# phy.net
KiCad netlist of a schematic drawn in Altium Designer
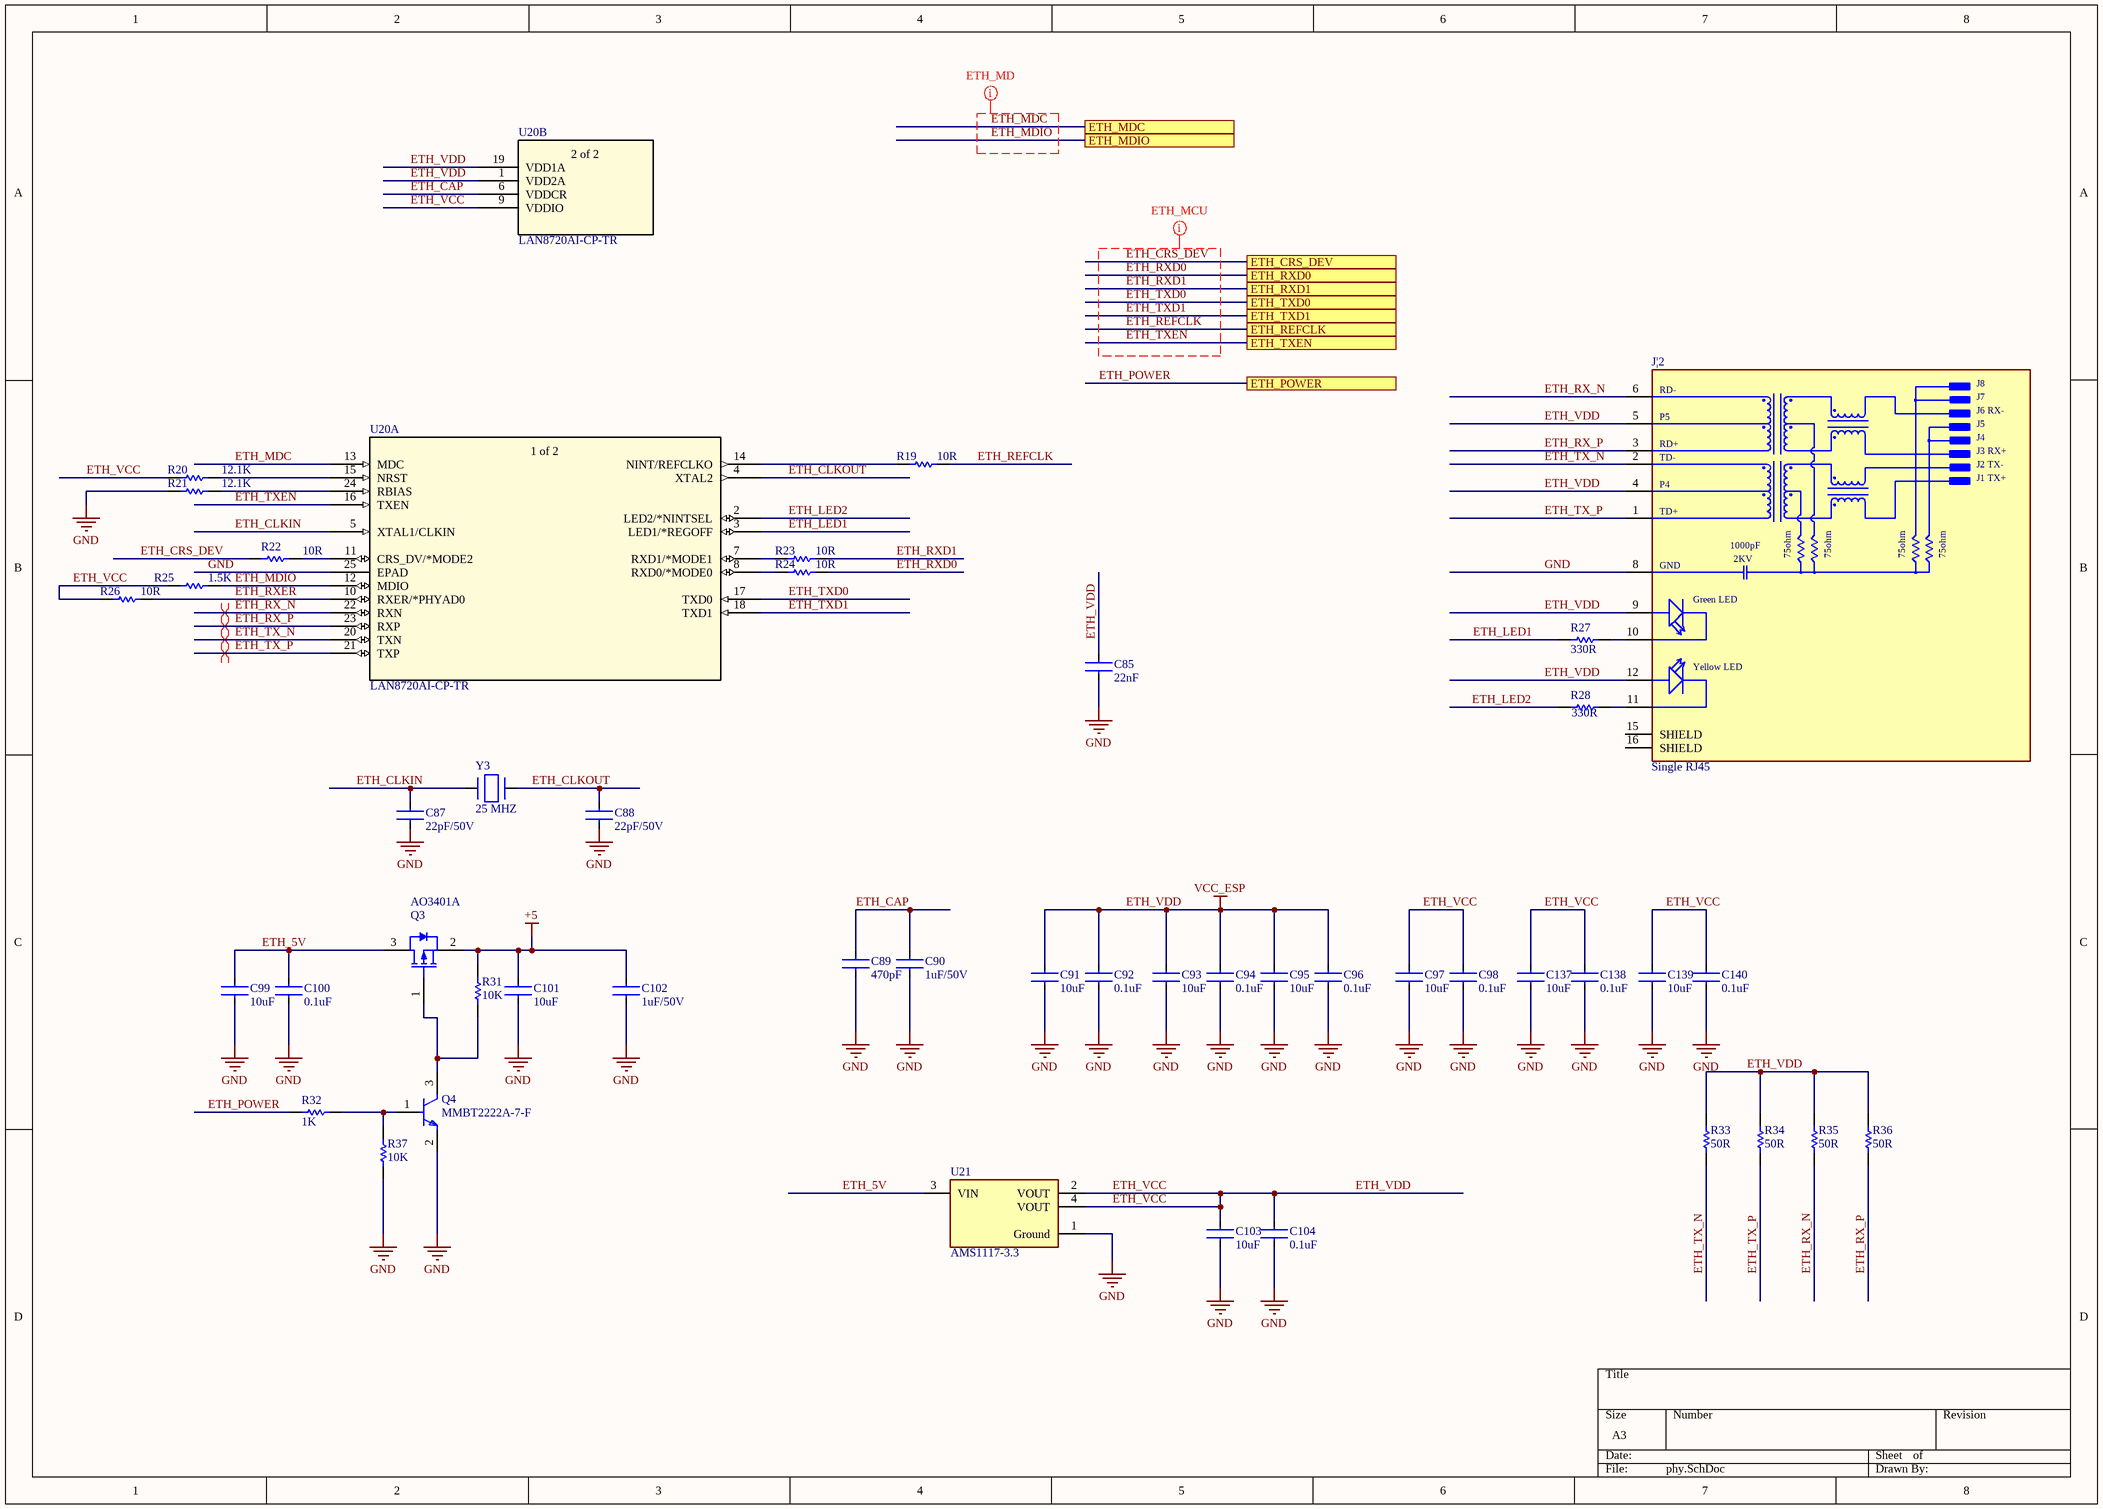
[diagram p0: phy.SchDoc]

(export (version "E")
  (design (tool "Eeschema 10.0.6"))
  (components
    (comp (ref "C85")
      (value "22nF")
      (footprint "C0402")
      (description "Cap Ceramic 22nF 50V C0G 5% SMD 1206 125°C Paper T/R")
      (fields
        (field (name "MANUFACTURER") "Samsung")
        (field (name "MANUFACTURER PART NUMBER") "CL31B223KBCNNNC")
      )
      (libsource (lib "afra") (part "CL31B223KBCNNNC"))
    )
    (comp (ref "C87")
      (value "22pF/50V")
      (footprint "C0402")
      (description "Cap Ceramic 22pF 50V C0G 5% SMD 1206 125°C Paper T/R")
      (fields
        (field (name "MANUFACTURER") "Samsung")
        (field (name "MANUFACTURER PART NUMBER") "CL31C220JBCNNNC")
      )
      (libsource (lib "afra") (part "CL31C220JBCNNNC"))
    )
    (comp (ref "C88")
      (value "22pF/50V")
      (footprint "C0402")
      (description "Cap Ceramic 22pF 50V C0G 5% SMD 1206 125°C Paper T/R")
      (fields
        (field (name "MANUFACTURER") "Samsung")
        (field (name "MANUFACTURER PART NUMBER") "CL31C220JBCNNNC")
      )
      (libsource (lib "afra") (part "CL31C220JBCNNNC"))
    )
    (comp (ref "C89")
      (value "470pF")
      (footprint "C0402")
      (description "Cap Ceramic 470pF 50V C0G 5% SMD 1206 125°C Paper T/R")
      (fields
        (field (name "MANUFACTURER") "Samsung")
        (field (name "MANUFACTURER PART NUMBER") "CL31C220JBCNNNC")
      )
      (libsource (lib "afra") (part "CL31B471KBCNNNC"))
    )
    (comp (ref "C90")
      (value "1uF/50V")
      (footprint "C0402")
      (description "CAP CER 1UF 50V X7R 1206")
      (fields
        (field (name "MANUFACTURER") "Samsung")
        (field (name "MANUFACTURER PART NUMBER") "CL31B105KBHNNNE")
      )
      (libsource (lib "afra") (part "CL31B105KBHNNNE"))
    )
    (comp (ref "C91")
      (value "10uF")
      (footprint "C0402")
      (description "Cap Ceramic 10uF 16V X7R 10% Pad SMD 1206 125°C T/R")
      (fields
        (field (name "MANUFACTURER") "Samsung")
        (field (name "MANUFACTURER PART NUMBER") "CL31B106KOHNNNE")
      )
      (libsource (lib "afra") (part "CL31B106KOHNNNE"))
    )
    (comp (ref "C92")
      (value "0.1uF")
      (footprint "C0402")
      (description "Ceramic capacitor SMD-1206 100nF /50V X7R# K +-10%, Samsung, RoHS")
      (fields
        (field (name "MANUFACTURER") "Samsung")
        (field (name "MANUFACTURER PART NUMBER") "CL31B104KBCNNNC")
      )
      (libsource (lib "afra") (part "CL31B104KBCNNNC"))
    )
    (comp (ref "C93")
      (value "10uF")
      (footprint "C0402")
      (description "Cap Ceramic 10uF 16V X7R 10% Pad SMD 1206 125°C T/R")
      (fields
        (field (name "MANUFACTURER") "Samsung")
        (field (name "MANUFACTURER PART NUMBER") "CL31B106KOHNNNE")
      )
      (libsource (lib "afra") (part "CL31B106KOHNNNE"))
    )
    (comp (ref "C94")
      (value "0.1uF")
      (footprint "C0402")
      (description "Ceramic capacitor SMD-1206 100nF /50V X7R# K +-10%, Samsung, RoHS")
      (fields
        (field (name "MANUFACTURER") "Samsung")
        (field (name "MANUFACTURER PART NUMBER") "CL31B104KBCNNNC")
      )
      (libsource (lib "afra") (part "CL31B104KBCNNNC"))
    )
    (comp (ref "C95")
      (value "10uF")
      (footprint "C0402")
      (description "Cap Ceramic 10uF 16V X7R 10% Pad SMD 1206 125°C T/R")
      (fields
        (field (name "MANUFACTURER") "Samsung")
        (field (name "MANUFACTURER PART NUMBER") "CL31B106KOHNNNE")
      )
      (libsource (lib "afra") (part "CL31B106KOHNNNE"))
    )
    (comp (ref "C96")
      (value "0.1uF")
      (footprint "C0402")
      (description "Ceramic capacitor SMD-1206 100nF /50V X7R# K +-10%, Samsung, RoHS")
      (fields
        (field (name "MANUFACTURER") "Samsung")
        (field (name "MANUFACTURER PART NUMBER") "CL31B104KBCNNNC")
      )
      (libsource (lib "afra") (part "CL31B104KBCNNNC"))
    )
    (comp (ref "C97")
      (value "10uF")
      (footprint "C0402")
      (description "Cap Ceramic 10uF 16V X7R 10% Pad SMD 1206 125°C T/R")
      (fields
        (field (name "MANUFACTURER") "Samsung")
        (field (name "MANUFACTURER PART NUMBER") "CL31B106KOHNNNE")
      )
      (libsource (lib "afra") (part "CL31B106KOHNNNE"))
    )
    (comp (ref "C98")
      (value "0.1uF")
      (footprint "C0402")
      (description "Ceramic capacitor SMD-1206 100nF /50V X7R# K +-10%, Samsung, RoHS")
      (fields
        (field (name "MANUFACTURER") "Samsung")
        (field (name "MANUFACTURER PART NUMBER") "CL31B104KBCNNNC")
      )
      (libsource (lib "afra") (part "CL31B104KBCNNNC"))
    )
    (comp (ref "C99")
      (value "10uF")
      (footprint "C0402")
      (description "Cap Ceramic 10uF 16V X7R 10% Pad SMD 1206 125°C T/R")
      (fields
        (field (name "MANUFACTURER") "Samsung")
        (field (name "MANUFACTURER PART NUMBER") "CL31B106KOHNNNE")
      )
      (libsource (lib "afra") (part "CL31B106KOHNNNE"))
    )
    (comp (ref "C100")
      (value "0.1uF")
      (footprint "C0402")
      (description "Ceramic capacitor SMD-1206 100nF /50V X7R# K +-10%, Samsung, RoHS")
      (fields
        (field (name "MANUFACTURER") "Samsung")
        (field (name "MANUFACTURER PART NUMBER") "CL31B104KBCNNNC")
      )
      (libsource (lib "afra") (part "CL31B104KBCNNNC"))
    )
    (comp (ref "C101")
      (value "10uF")
      (footprint "C0402")
      (description "Cap Ceramic 10uF 16V X7R 10% Pad SMD 1206 125°C T/R")
      (fields
        (field (name "MANUFACTURER") "Samsung")
        (field (name "MANUFACTURER PART NUMBER") "CL31B106KOHNNNE")
      )
      (libsource (lib "afra") (part "CL31B106KOHNNNE"))
    )
    (comp (ref "C102")
      (value "1uF/50V")
      (footprint "C0402")
      (description "CAP CER 1UF 50V X7R 1206")
      (fields
        (field (name "MANUFACTURER") "Samsung")
        (field (name "MANUFACTURER PART NUMBER") "CL31B105KBHNNNE")
      )
      (libsource (lib "afra") (part "CL31B105KBHNNNE"))
    )
    (comp (ref "C103")
      (value "10uF")
      (footprint "C0402")
      (description "Cap Ceramic 10uF 16V X7R 10% Pad SMD 1206 125°C T/R")
      (fields
        (field (name "MANUFACTURER") "Samsung")
        (field (name "MANUFACTURER PART NUMBER") "CL31B106KOHNNNE")
      )
      (libsource (lib "afra") (part "CL31B106KOHNNNE"))
    )
    (comp (ref "C104")
      (value "0.1uF")
      (footprint "C0402")
      (description "Ceramic capacitor SMD-1206 100nF /50V X7R# K +-10%, Samsung, RoHS")
      (fields
        (field (name "MANUFACTURER") "Samsung")
        (field (name "MANUFACTURER PART NUMBER") "CL31B104KBCNNNC")
      )
      (libsource (lib "afra") (part "CL31B104KBCNNNC"))
    )
    (comp (ref "C137")
      (value "10uF")
      (footprint "C0402")
      (description "Cap Ceramic 10uF 16V X7R 10% Pad SMD 1206 125°C T/R")
      (fields
        (field (name "MANUFACTURER") "Samsung")
        (field (name "MANUFACTURER PART NUMBER") "CL31B106KOHNNNE")
      )
      (libsource (lib "afra") (part "CL31B106KOHNNNE"))
    )
    (comp (ref "C138")
      (value "0.1uF")
      (footprint "C0402")
      (description "Ceramic capacitor SMD-1206 100nF /50V X7R# K +-10%, Samsung, RoHS")
      (fields
        (field (name "MANUFACTURER") "Samsung")
        (field (name "MANUFACTURER PART NUMBER") "CL31B104KBCNNNC")
      )
      (libsource (lib "afra") (part "CL31B104KBCNNNC"))
    )
    (comp (ref "C139")
      (value "10uF")
      (footprint "C0402")
      (description "Cap Ceramic 10uF 16V X7R 10% Pad SMD 1206 125°C T/R")
      (fields
        (field (name "MANUFACTURER") "Samsung")
        (field (name "MANUFACTURER PART NUMBER") "CL31B106KOHNNNE")
      )
      (libsource (lib "afra") (part "CL31B106KOHNNNE"))
    )
    (comp (ref "C140")
      (value "0.1uF")
      (footprint "C0402")
      (description "Ceramic capacitor SMD-1206 100nF /50V X7R# K +-10%, Samsung, RoHS")
      (fields
        (field (name "MANUFACTURER") "Samsung")
        (field (name "MANUFACTURER PART NUMBER") "CL31B104KBCNNNC")
      )
      (libsource (lib "afra") (part "CL31B104KBCNNNC"))
    )
    (comp (ref "J¦2")
      (value "Single RJ45")
      (footprint "HANRUN_HR911105A")
      (description "HR911105A Ethernet Interface Arduino Platform Evaluation Expansion Board")
      (fields (field (name "MP") "HR911105A") (field (name "MF") "DFRobot"))
      (libsource (lib "afra") (part "HR911105A"))
    )
    (comp (ref "Q3")
      (value "AO3401A")
      (footprint "SOT-23-3L_AOS")
      (description "No Description Available")
      (fields (field (name "COPYRIGHT") "Copyright (C) 2022 Ultra Librarian. All rights reserved."))
      (libsource (lib "afra") (part "AO3401A"))
    )
    (comp (ref "Q4")
      (value "MMBT2222A-7-F")
      (footprint "SOT-23-3L_AOS")
      (description "NPN Ic=600mA Vceo=40V hfe=100~300 fT=300MHz P=310mW SOT-23")
      (fields (field (name "MANUFACTURER") "Diodes") (field (name "VOLTAGE") "40V"))
      (libsource (lib "afra") (part "MMBT2222A-7-F"))
    )
    (comp (ref "R19")
      (value "10R")
      (footprint "R0402")
      (description "Res Thick Film 1206 10 Ohm 1% 0.25W(1/4W) +/-200ppm/ßC Epoxy SMD T/R")
      (fields
        (field (name "MANUFACTURER") "Yageo")
        (field (name "MANUFACTURER PART NUMBER") "RC1206FR-0710RL")
      )
      (libsource (lib "afra") (part "RC1206FR-0710RL"))
    )
    (comp (ref "R20")
      (value "12.1K")
      (footprint "R0402")
      (description "Res Thick Film 1206 12.1K Ohm 1% 0.25W(1/4W) ±100ppm/C Pad SMD T/R")
      (fields
        (field (name "MANUFACTURER") "Yageo")
        (field (name "MANUFACTURER PART NUMBER") "RC1206FR-072K2L")
      )
      (libsource (lib "afra") (part "RC1206FR-0712K1L"))
    )
    (comp (ref "R21")
      (value "12.1K")
      (footprint "R0402")
      (description "Res Thick Film 1206 12.1K Ohm 1% 0.25W(1/4W) ±100ppm/C Pad SMD T/R")
      (fields
        (field (name "MANUFACTURER") "Yageo")
        (field (name "MANUFACTURER PART NUMBER") "RC1206FR-072K2L")
      )
      (libsource (lib "afra") (part "RC1206FR-0712K1L"))
    )
    (comp (ref "R22")
      (value "10R")
      (footprint "R0402")
      (description "Res Thick Film 1206 10 Ohm 1% 0.25W(1/4W) +/-200ppm/ßC Epoxy SMD T/R")
      (fields
        (field (name "MANUFACTURER") "Yageo")
        (field (name "MANUFACTURER PART NUMBER") "RC1206FR-0710RL")
      )
      (libsource (lib "afra") (part "RC1206FR-0710RL"))
    )
    (comp (ref "R23")
      (value "10R")
      (footprint "R0402")
      (description "Res Thick Film 1206 10 Ohm 1% 0.25W(1/4W) +/-200ppm/ßC Epoxy SMD T/R")
      (fields
        (field (name "MANUFACTURER") "Yageo")
        (field (name "MANUFACTURER PART NUMBER") "RC1206FR-0710RL")
      )
      (libsource (lib "afra") (part "RC1206FR-0710RL"))
    )
    (comp (ref "R24")
      (value "10R")
      (footprint "R0402")
      (description "Res Thick Film 1206 10 Ohm 1% 0.25W(1/4W) +/-200ppm/ßC Epoxy SMD T/R")
      (fields
        (field (name "MANUFACTURER") "Yageo")
        (field (name "MANUFACTURER PART NUMBER") "RC1206FR-0710RL")
      )
      (libsource (lib "afra") (part "RC1206FR-0710RL"))
    )
    (comp (ref "R25")
      (value "1.5K")
      (footprint "R0402")
      (description "In a Pack of 5000, 1.5K 1206 Thick Film SMD Resistor ±1% 0.25W - RC1206FR-071KL")
      (fields
        (field (name "MANUFACTURER") "Yageo")
        (field (name "MANUFACTURER PART NUMBER") "RC1206FR-071KL")
      )
      (libsource (lib "afra") (part "RC1206FR-071K5L"))
    )
    (comp (ref "R26")
      (value "10R")
      (footprint "R0402")
      (description "Res Thick Film 1206 10 Ohm 1% 0.25W(1/4W) +/-200ppm/ßC Epoxy SMD T/R")
      (fields
        (field (name "MANUFACTURER") "Yageo")
        (field (name "MANUFACTURER PART NUMBER") "RC1206FR-0710RL")
      )
      (libsource (lib "afra") (part "RC1206FR-0710RL"))
    )
    (comp (ref "R27")
      (value "330R")
      (footprint "R0402")
      (description "Res Thick Film 1206 330 Ohm 1% 0.25W(1/4W) ±100ppm/°C Pad SMD T/R")
      (fields
        (field (name "MANUFACTURER") "Yageo")
        (field (name "MANUFACTURER PART NUMBER") "RC1206FR-07330RL")
      )
      (libsource (lib "afra") (part "RC1206FR-07330RL"))
    )
    (comp (ref "R28")
      (value "330R")
      (footprint "R0402")
      (description "Res Thick Film 1206 330 Ohm 1% 0.25W(1/4W) ±100ppm/°C Pad SMD T/R")
      (fields
        (field (name "MANUFACTURER") "Yageo")
        (field (name "MANUFACTURER PART NUMBER") "RC1206FR-07330RL")
      )
      (libsource (lib "afra") (part "RC1206FR-07330RL"))
    )
    (comp (ref "R31")
      (value "10K")
      (footprint "R0402")
      (description "Res Thick Film 1206 10K Ohm 1% 0.25W(1/4W) ±100ppm/C Pad SMD T/R")
      (fields
        (field (name "MANUFACTURER") "Yageo")
        (field (name "MANUFACTURER PART NUMBER") "RC1206FR-0710KL")
      )
      (libsource (lib "afra") (part "RC1206FR-0710KL"))
    )
    (comp (ref "R32")
      (value "1K")
      (footprint "R0402")
      (description "In a Pack of 5000, 1K 1206 Thick Film SMD Resistor ±1% 0.25W - RC1206FR-071KL")
      (fields
        (field (name "MANUFACTURER") "Yageo")
        (field (name "MANUFACTURER PART NUMBER") "RC1206FR-071KL")
      )
      (libsource (lib "afra") (part "RC1206FR-071KL"))
    )
    (comp (ref "R33")
      (value "50R")
      (footprint "R0402")
      (description "Res Thick Film 1206 50 Ohm 1% 0.25W(1/4W) +/-200ppm/ßC Epoxy SMD T/R")
      (fields
        (field (name "MANUFACTURER") "Yageo")
        (field (name "MANUFACTURER PART NUMBER") "RC1206FR-0710RL")
      )
      (libsource (lib "afra") (part "RC1206FR-0750RL"))
    )
    (comp (ref "R34")
      (value "50R")
      (footprint "R0402")
      (description "Res Thick Film 1206 50 Ohm 1% 0.25W(1/4W) +/-200ppm/ßC Epoxy SMD T/R")
      (fields
        (field (name "MANUFACTURER") "Yageo")
        (field (name "MANUFACTURER PART NUMBER") "RC1206FR-0710RL")
      )
      (libsource (lib "afra") (part "RC1206FR-0750RL"))
    )
    (comp (ref "R35")
      (value "50R")
      (footprint "R0402")
      (description "Res Thick Film 1206 50 Ohm 1% 0.25W(1/4W) +/-200ppm/ßC Epoxy SMD T/R")
      (fields
        (field (name "MANUFACTURER") "Yageo")
        (field (name "MANUFACTURER PART NUMBER") "RC1206FR-0710RL")
      )
      (libsource (lib "afra") (part "RC1206FR-0750RL"))
    )
    (comp (ref "R36")
      (value "50R")
      (footprint "R0402")
      (description "Res Thick Film 1206 50 Ohm 1% 0.25W(1/4W) +/-200ppm/ßC Epoxy SMD T/R")
      (fields
        (field (name "MANUFACTURER") "Yageo")
        (field (name "MANUFACTURER PART NUMBER") "RC1206FR-0710RL")
      )
      (libsource (lib "afra") (part "RC1206FR-0750RL"))
    )
    (comp (ref "R37")
      (value "10K")
      (footprint "R0402")
      (description "Res Thick Film 1206 10K Ohm 1% 0.25W(1/4W) ±100ppm/C Pad SMD T/R")
      (fields
        (field (name "MANUFACTURER") "Yageo")
        (field (name "MANUFACTURER PART NUMBER") "RC1206FR-0710KL")
      )
      (libsource (lib "afra") (part "RC1206FR-0710KL"))
    )
    (comp (ref "U20")
      (value "LAN8720AI-CP-TR")
      (footprint "QFN24-6X6_MC_MCH")
      (description "No Description Available")
      (fields (field (name "COPYRIGHT") "Copyright (C) 2022 Ultra Librarian. All rights reserved."))
      (libsource (lib "afra") (part "LAN8720AI-CP-TR"))
    )
    (comp (ref "U21")
      (value "AMS1117-3.3")
      (footprint "Advanced_Monolithic_Systems_AMS1117_IPC_A")
      (description "Fixed 15V 3.3V 1.3V @ 800mA SOT-223 Dropout Regulators(LDO) RoHS")
      (libsource (lib "afra") (part "AMS1117-3.3"))
    )
    (comp (ref "Y3")
      (value "25 MHZ")
      (footprint "CTS_ATS080B_0")
      (description "CRYSTAL 25.000MHZ 20PF THRU")
      (fields (field (name "MANUFACTURER") "TXC") (field (name "MANUFACTURER PART NUMBER") "9B-8.000MBBK-B"))
      (libsource (lib "afra") (part "CRYSTAL 25.000MHZ"))
    )
  )
  (nets
    (net (code "1") (name "+5") (class "Default")
      (node (ref "C101") (pin "1") (pinfunction "1_1") (pintype "passive"))
      (node (ref "C102") (pin "1") (pinfunction "1_1") (pintype "passive"))
      (node (ref "Q3") (pin "2") (pinfunction "S_2") (pintype "passive"))
      (node (ref "R31") (pin "2") (pinfunction "2_2") (pintype "passive"))
    )
    (net (code "2") (name "/ETH_5V") (class "Default")
      (node (ref "C100") (pin "1") (pinfunction "1_1") (pintype "passive"))
      (node (ref "C99") (pin "1") (pinfunction "1_1") (pintype "passive"))
      (node (ref "Q3") (pin "3") (pinfunction "D_3") (pintype "passive"))
      (node (ref "U21") (pin "3") (pinfunction "VIN_3") (pintype "power_in"))
    )
    (net (code "3") (name "/ETH_CAP") (class "Default")
      (node (ref "C89") (pin "1") (pinfunction "1_1") (pintype "passive"))
      (node (ref "C90") (pin "1") (pinfunction "1_1") (pintype "passive"))
      (node (ref "U20") (pin "6") (pinfunction "VDDCR_6") (pintype "power_in"))
    )
    (net (code "4") (name "/ETH_CLKIN") (class "Default")
      (node (ref "C87") (pin "1") (pinfunction "1_1") (pintype "passive"))
      (node (ref "U20") (pin "5") (pinfunction "XTAL1/CLKIN_5") (pintype "input"))
      (node (ref "Y3") (pin "1") (pinfunction "1_1") (pintype "passive"))
    )
    (net (code "5") (name "/ETH_CLKOUT") (class "Default")
      (node (ref "C88") (pin "1") (pinfunction "1_1") (pintype "passive"))
      (node (ref "U20") (pin "4") (pinfunction "XTAL2_4") (pintype "output"))
      (node (ref "Y3") (pin "2") (pinfunction "2_2") (pintype "passive"))
    )
    (net (code "6") (name "/ETH_CRS_DEV") (class "Default")
      (node (ref "R22") (pin "1") (pinfunction "1_1") (pintype "passive"))
    )
    (net (code "7") (name "/ETH_LED1") (class "Default")
      (node (ref "R27") (pin "2") (pinfunction "2_2") (pintype "passive"))
      (node (ref "U20") (pin "3") (pinfunction "LED1/*REGOFF_3") (pintype "bidirectional"))
    )
    (net (code "8") (name "/ETH_LED2") (class "Default")
      (node (ref "R28") (pin "1") (pinfunction "1_1") (pintype "passive"))
      (node (ref "U20") (pin "2") (pinfunction "LED2/*NINTSEL_2") (pintype "bidirectional"))
    )
    (net (code "9") (name "/ETH_MDC") (class "Default")
      (node (ref "U20") (pin "13") (pinfunction "MDC_13") (pintype "input"))
    )
    (net (code "10") (name "/ETH_MDIO") (class "Default")
      (node (ref "R25") (pin "2") (pinfunction "2_2") (pintype "passive"))
      (node (ref "U20") (pin "12") (pinfunction "MDIO_12") (pintype "bidirectional"))
    )
    (net (code "11") (name "/ETH_POWER") (class "Default")
      (node (ref "R32") (pin "1") (pinfunction "1_1") (pintype "passive"))
    )
    (net (code "12") (name "/ETH_REFCLK") (class "Default")
      (node (ref "R19") (pin "2") (pinfunction "2_2") (pintype "passive"))
    )
    (net (code "13") (name "/ETH_RXD0") (class "Default")
      (node (ref "R24") (pin "2") (pinfunction "2_2") (pintype "passive"))
    )
    (net (code "14") (name "/ETH_RXD1") (class "Default")
      (node (ref "R23") (pin "2") (pinfunction "2_2") (pintype "passive"))
    )
    (net (code "15") (name "/ETH_RXER") (class "Default")
      (node (ref "R26") (pin "2") (pinfunction "2_2") (pintype "passive"))
      (node (ref "U20") (pin "10") (pinfunction "RXER/*PHYAD0_10") (pintype "bidirectional"))
    )
    (net (code "16") (name "/ETH_RX_N") (class "Default")
      (node (ref "J¦2") (pin "6") (pinfunction "RD-_6") (pintype "passive"))
      (node (ref "R35") (pin "1") (pinfunction "1_1") (pintype "passive"))
      (node (ref "U20") (pin "22") (pinfunction "RXN_22") (pintype "bidirectional"))
    )
    (net (code "17") (name "/ETH_RX_P") (class "Default")
      (node (ref "J¦2") (pin "3") (pinfunction "RD+_3") (pintype "passive"))
      (node (ref "R36") (pin "1") (pinfunction "1_1") (pintype "passive"))
      (node (ref "U20") (pin "23") (pinfunction "RXP_23") (pintype "bidirectional"))
    )
    (net (code "18") (name "/ETH_TXD0") (class "Default")
      (node (ref "U20") (pin "17") (pinfunction "TXD0_17") (pintype "input"))
    )
    (net (code "19") (name "/ETH_TXD1") (class "Default")
      (node (ref "U20") (pin "18") (pinfunction "TXD1_18") (pintype "input"))
    )
    (net (code "20") (name "/ETH_TXEN") (class "Default")
      (node (ref "U20") (pin "16") (pinfunction "TXEN_16") (pintype "input"))
    )
    (net (code "21") (name "/ETH_TX_N") (class "Default")
      (node (ref "J¦2") (pin "2") (pinfunction "TD-_2") (pintype "passive"))
      (node (ref "R33") (pin "1") (pinfunction "1_1") (pintype "passive"))
      (node (ref "U20") (pin "20") (pinfunction "TXN_20") (pintype "bidirectional"))
    )
    (net (code "22") (name "/ETH_TX_P") (class "Default")
      (node (ref "J¦2") (pin "1") (pinfunction "TD+_1") (pintype "passive"))
      (node (ref "R34") (pin "1") (pinfunction "1_1") (pintype "passive"))
      (node (ref "U20") (pin "21") (pinfunction "TXP_21") (pintype "bidirectional"))
    )
    (net (code "23") (name "GND") (class "Default")
      (node (ref "C100") (pin "2") (pinfunction "2_2") (pintype "passive"))
      (node (ref "C101") (pin "2") (pinfunction "2_2") (pintype "passive"))
      (node (ref "C102") (pin "2") (pinfunction "2_2") (pintype "passive"))
      (node (ref "C103") (pin "2") (pinfunction "2_2") (pintype "passive"))
      (node (ref "C104") (pin "2") (pinfunction "2_2") (pintype "passive"))
      (node (ref "C137") (pin "2") (pinfunction "2_2") (pintype "passive"))
      (node (ref "C138") (pin "2") (pinfunction "2_2") (pintype "passive"))
      (node (ref "C139") (pin "2") (pinfunction "2_2") (pintype "passive"))
      (node (ref "C140") (pin "2") (pinfunction "2_2") (pintype "passive"))
      (node (ref "C85") (pin "2") (pinfunction "2_2") (pintype "passive"))
      (node (ref "C87") (pin "2") (pinfunction "2_2") (pintype "passive"))
      (node (ref "C88") (pin "2") (pinfunction "2_2") (pintype "passive"))
      (node (ref "C89") (pin "2") (pinfunction "2_2") (pintype "passive"))
      (node (ref "C90") (pin "2") (pinfunction "2_2") (pintype "passive"))
      (node (ref "C91") (pin "2") (pinfunction "2_2") (pintype "passive"))
      (node (ref "C92") (pin "2") (pinfunction "2_2") (pintype "passive"))
      (node (ref "C93") (pin "2") (pinfunction "2_2") (pintype "passive"))
      (node (ref "C94") (pin "2") (pinfunction "2_2") (pintype "passive"))
      (node (ref "C95") (pin "2") (pinfunction "2_2") (pintype "passive"))
      (node (ref "C96") (pin "2") (pinfunction "2_2") (pintype "passive"))
      (node (ref "C97") (pin "2") (pinfunction "2_2") (pintype "passive"))
      (node (ref "C98") (pin "2") (pinfunction "2_2") (pintype "passive"))
      (node (ref "C99") (pin "2") (pinfunction "2_2") (pintype "passive"))
      (node (ref "J¦2") (pin "8") (pinfunction "GND_8") (pintype "power_in"))
      (node (ref "Q4") (pin "2") (pinfunction "E_2") (pintype "passive"))
      (node (ref "R21") (pin "1") (pinfunction "1_1") (pintype "passive"))
      (node (ref "R37") (pin "1") (pinfunction "1_1") (pintype "passive"))
      (node (ref "U20") (pin "25") (pinfunction "EPAD_25") (pintype "passive"))
      (node (ref "U21") (pin "1") (pinfunction "Ground_1") (pintype "power_in"))
    )
    (net (code "24") (name "Net-(J¦2-GC)") (class "Default")
      (node (ref "J¦2") (pin "10") (pinfunction "GC_10") (pintype "passive"))
      (node (ref "R27") (pin "1") (pinfunction "1_1") (pintype "passive"))
    )
    (net (code "25") (name "Net-(J¦2-YC)") (class "Default")
      (node (ref "J¦2") (pin "11") (pinfunction "YC_11") (pintype "passive"))
      (node (ref "R28") (pin "2") (pinfunction "2_2") (pintype "passive"))
    )
    (net (code "26") (name "Net-(Q3-G)") (class "Default")
      (node (ref "Q3") (pin "1") (pinfunction "G_1") (pintype "passive"))
      (node (ref "Q4") (pin "3") (pinfunction "C_3") (pintype "passive"))
      (node (ref "R31") (pin "1") (pinfunction "1_1") (pintype "passive"))
    )
    (net (code "27") (name "Net-(Q4-B)") (class "Default")
      (node (ref "Q4") (pin "1") (pinfunction "B_1") (pintype "passive"))
      (node (ref "R32") (pin "2") (pinfunction "2_2") (pintype "passive"))
      (node (ref "R37") (pin "2") (pinfunction "2_2") (pintype "passive"))
    )
    (net (code "28") (name "Net-(U20A-CRS_DV{slash}*MODE2)") (class "Default")
      (node (ref "R22") (pin "2") (pinfunction "2_2") (pintype "passive"))
      (node (ref "U20") (pin "11") (pinfunction "CRS_DV/*MODE2_11") (pintype "bidirectional"))
    )
    (net (code "29") (name "Net-(U20A-NINT{slash}REFCLKO)") (class "Default")
      (node (ref "R19") (pin "1") (pinfunction "1_1") (pintype "passive"))
      (node (ref "U20") (pin "14") (pinfunction "NINT/REFCLKO_14") (pintype "output"))
    )
    (net (code "30") (name "Net-(U20A-NRST)") (class "Default")
      (node (ref "R20") (pin "2") (pinfunction "2_2") (pintype "passive"))
      (node (ref "U20") (pin "15") (pinfunction "NRST_15") (pintype "input"))
    )
    (net (code "31") (name "Net-(U20A-RBIAS)") (class "Default")
      (node (ref "R21") (pin "2") (pinfunction "2_2") (pintype "passive"))
      (node (ref "U20") (pin "24") (pinfunction "RBIAS_24") (pintype "input"))
    )
    (net (code "32") (name "Net-(U20A-RXD0{slash}*MODE0)") (class "Default")
      (node (ref "R24") (pin "1") (pinfunction "1_1") (pintype "passive"))
      (node (ref "U20") (pin "8") (pinfunction "RXD0/*MODE0_8") (pintype "bidirectional"))
    )
    (net (code "33") (name "Net-(U20A-RXD1{slash}*MODE1)") (class "Default")
      (node (ref "R23") (pin "1") (pinfunction "1_1") (pintype "passive"))
      (node (ref "U20") (pin "7") (pinfunction "RXD1/*MODE1_7") (pintype "bidirectional"))
    )
    (net (code "34") (name "VCC_ESP") (class "Default")
      (node (ref "C103") (pin "1") (pinfunction "1_1") (pintype "passive"))
      (node (ref "C104") (pin "1") (pinfunction "1_1") (pintype "passive"))
      (node (ref "C137") (pin "1") (pinfunction "1_1") (pintype "passive"))
      (node (ref "C138") (pin "1") (pinfunction "1_1") (pintype "passive"))
      (node (ref "C139") (pin "1") (pinfunction "1_1") (pintype "passive"))
      (node (ref "C140") (pin "1") (pinfunction "1_1") (pintype "passive"))
      (node (ref "C85") (pin "1") (pinfunction "1_1") (pintype "passive"))
      (node (ref "C91") (pin "1") (pinfunction "1_1") (pintype "passive"))
      (node (ref "C92") (pin "1") (pinfunction "1_1") (pintype "passive"))
      (node (ref "C93") (pin "1") (pinfunction "1_1") (pintype "passive"))
      (node (ref "C94") (pin "1") (pinfunction "1_1") (pintype "passive"))
      (node (ref "C95") (pin "1") (pinfunction "1_1") (pintype "passive"))
      (node (ref "C96") (pin "1") (pinfunction "1_1") (pintype "passive"))
      (node (ref "C97") (pin "1") (pinfunction "1_1") (pintype "passive"))
      (node (ref "C98") (pin "1") (pinfunction "1_1") (pintype "passive"))
      (node (ref "J¦2") (pin "12") (pinfunction "YA_12") (pintype "passive"))
      (node (ref "J¦2") (pin "4") (pinfunction "P4_4") (pintype "passive"))
      (node (ref "J¦2") (pin "5") (pinfunction "P5_5") (pintype "passive"))
      (node (ref "J¦2") (pin "9") (pinfunction "GA_9") (pintype "passive"))
      (node (ref "R20") (pin "1") (pinfunction "1_1") (pintype "passive"))
      (node (ref "R25") (pin "1") (pinfunction "1_1") (pintype "passive"))
      (node (ref "R26") (pin "1") (pinfunction "1_1") (pintype "passive"))
      (node (ref "R33") (pin "2") (pinfunction "2_2") (pintype "passive"))
      (node (ref "R34") (pin "2") (pinfunction "2_2") (pintype "passive"))
      (node (ref "R35") (pin "2") (pinfunction "2_2") (pintype "passive"))
      (node (ref "R36") (pin "2") (pinfunction "2_2") (pintype "passive"))
      (node (ref "U20") (pin "1") (pinfunction "VDD2A_1") (pintype "power_in"))
      (node (ref "U20") (pin "19") (pinfunction "VDD1A_19") (pintype "power_in"))
      (node (ref "U20") (pin "9") (pinfunction "VDDIO_9") (pintype "power_in"))
      (node (ref "U21") (pin "2") (pinfunction "VOUT_2") (pintype "passive"))
      (node (ref "U21") (pin "4") (pinfunction "VOUT_4") (pintype "passive"))
    )
    (net (code "35") (name "unconnected-(J¦2-SHIELD-Pad15)") (class "Default")
      (node (ref "J¦2") (pin "15") (pinfunction "SHIELD_15") (pintype "passive"))
    )
    (net (code "36") (name "unconnected-(J¦2-SHIELD-Pad16)") (class "Default")
      (node (ref "J¦2") (pin "16") (pinfunction "SHIELD_16") (pintype "passive"))
    )
  )
)
